# Flyback_schematic.net
KiCad netlist of a schematic drawn in Altium Designer
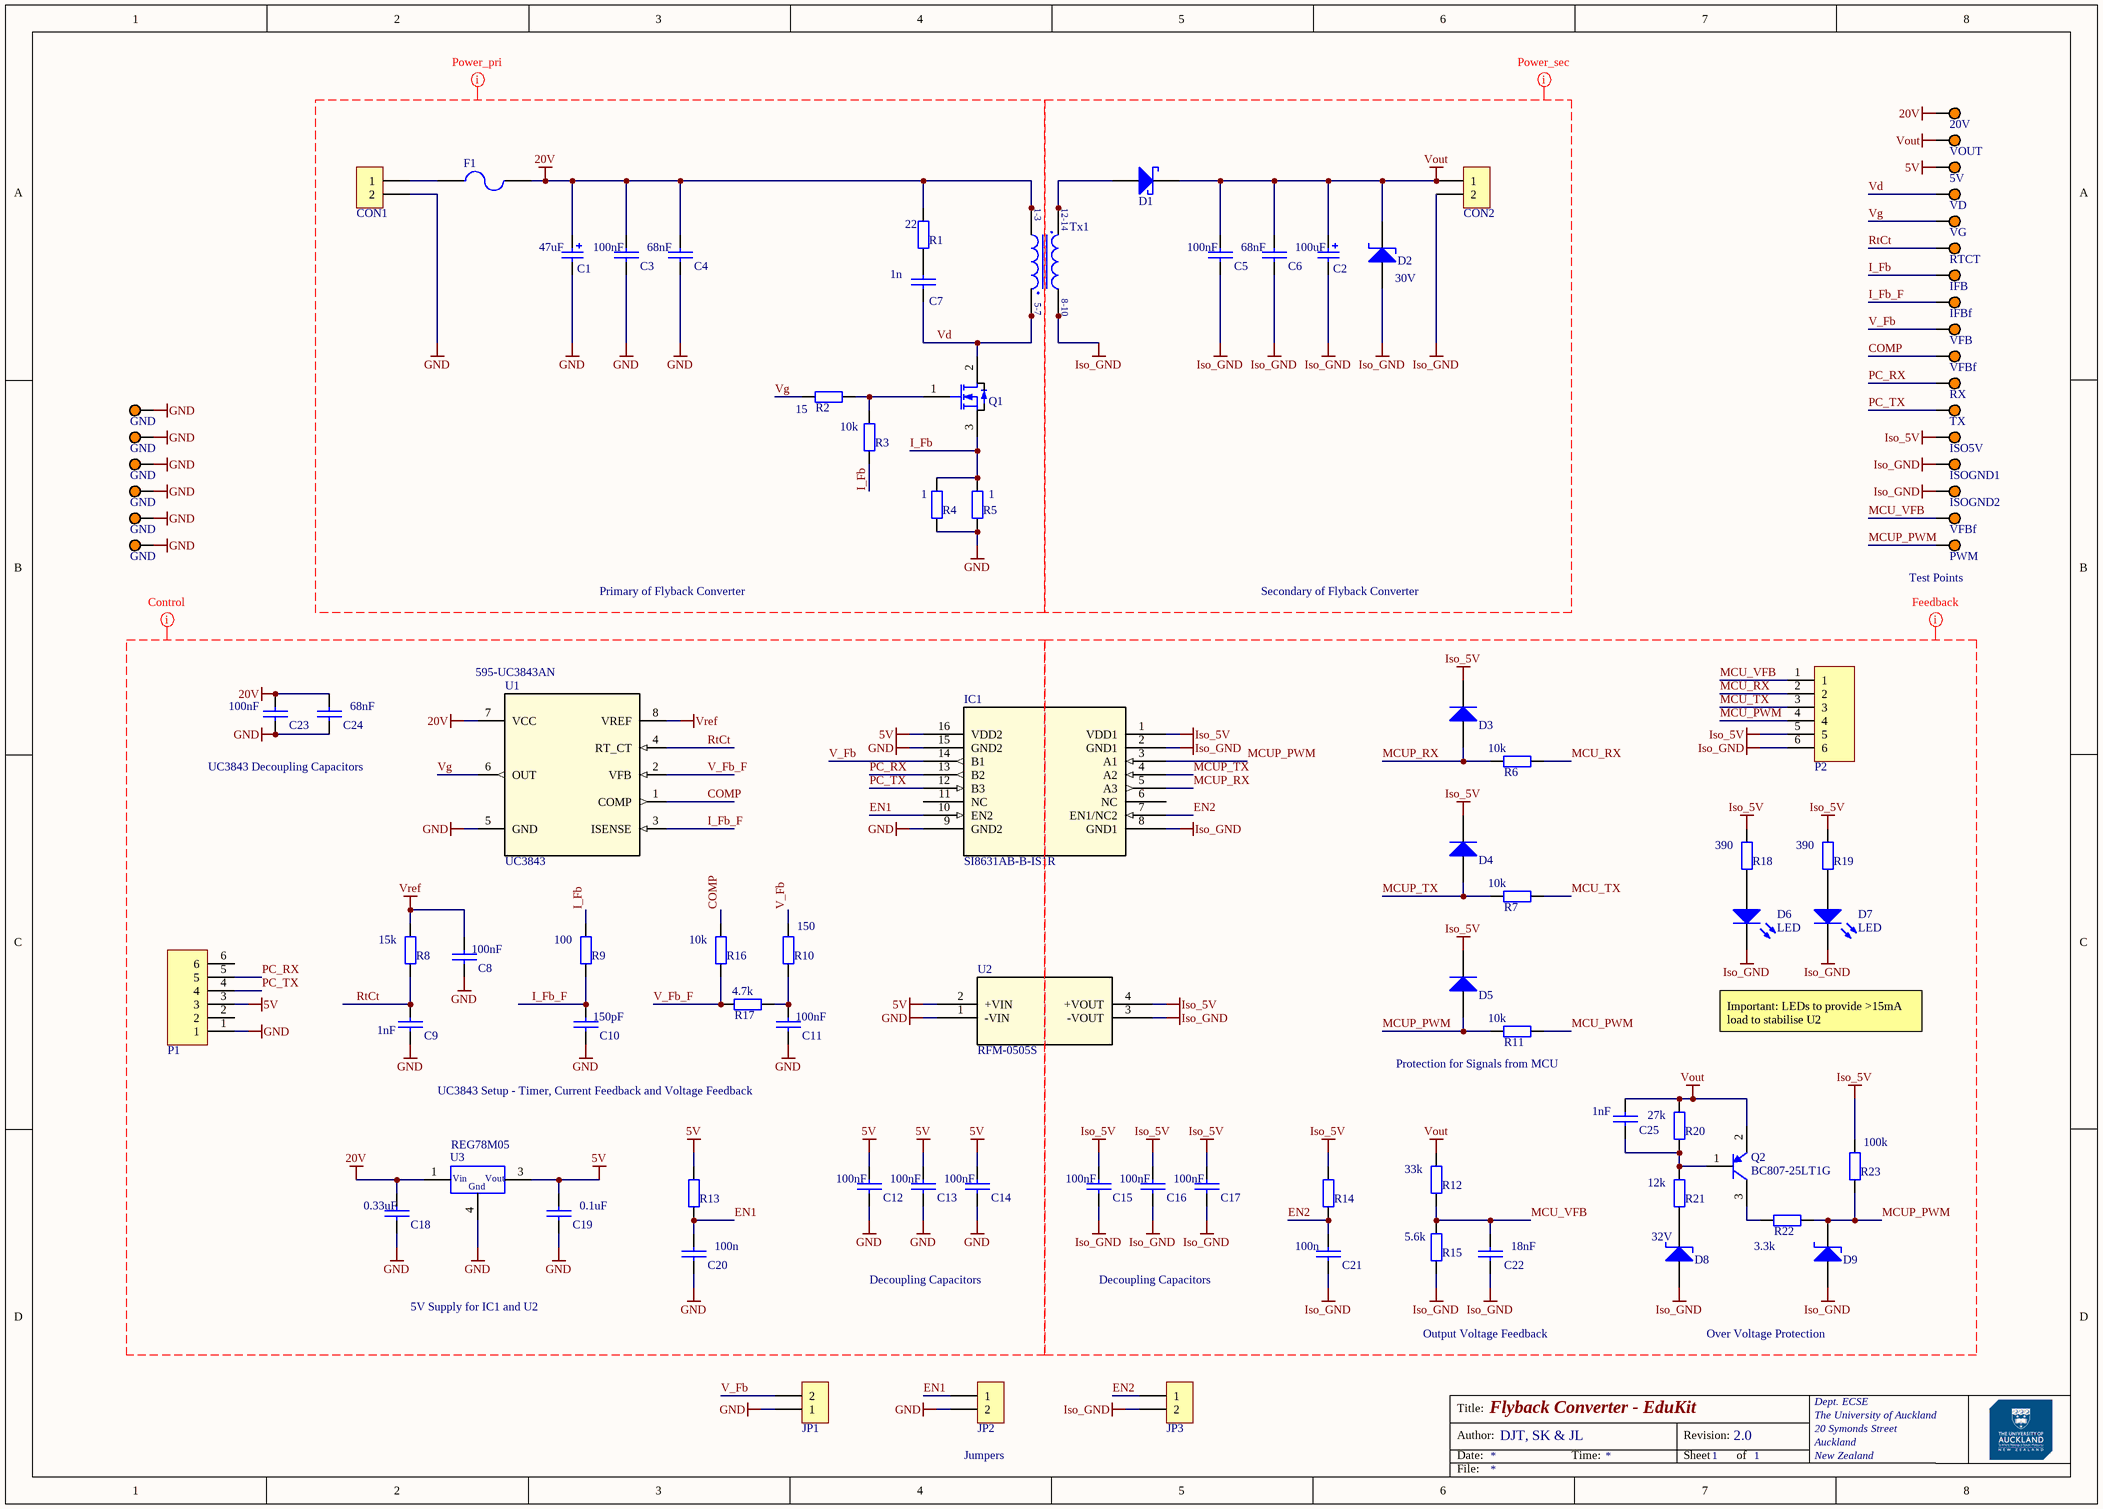
[diagram p0: Flyback_schematic.SchDoc]

(export (version "E")
  (design (tool "Eeschema 10.0.6"))
  (components
    (comp (ref "C1")
      (value "47uF")
      (footprint "CR05")
      (description "ECAP")
      (libsource (lib "EE311_library") (part "ECAP"))
    )
    (comp (ref "C2")
      (value "100uF")
      (footprint "CR05")
      (description "ECAP")
      (libsource (lib "EE311_library") (part "ECAP"))
    )
    (comp (ref "C3")
      (value "100nF")
      (footprint "C1210")
      (description "CCAP1210")
      (libsource (lib "EE311_library") (part "CCAP1210"))
    )
    (comp (ref "C4")
      (value "68nF")
      (footprint "C1210")
      (description "CCAP1210")
      (libsource (lib "EE311_library") (part "CCAP1210"))
    )
    (comp (ref "C5")
      (value "100nF")
      (footprint "C1210")
      (description "CCAP1210")
      (libsource (lib "EE311_library") (part "CCAP1210"))
    )
    (comp (ref "C6")
      (value "68nF")
      (footprint "C1210")
      (description "CCAP1210")
      (libsource (lib "EE311_library") (part "CCAP1210"))
    )
    (comp (ref "C7")
      (value "1n")
      (footprint "C1210")
      (description "CCAP1210")
      (libsource (lib "EE311_library") (part "CCAP1210"))
    )
    (comp (ref "C8")
      (value "100nF")
      (footprint "C0805")
      (description "CCAP0805")
      (libsource (lib "EE311_library") (part "CCAP0805"))
    )
    (comp (ref "C9")
      (value "1nF")
      (footprint "C0805")
      (description "CCAP0805")
      (libsource (lib "EE311_library") (part "CCAP0805"))
    )
    (comp (ref "C10")
      (value "150pF")
      (footprint "C0805")
      (description "CCAP0805")
      (libsource (lib "EE311_library") (part "CCAP0805"))
    )
    (comp (ref "C11")
      (value "100nF")
      (footprint "C0805")
      (description "CCAP0805")
      (libsource (lib "EE311_library") (part "CCAP0805"))
    )
    (comp (ref "C12")
      (value "100nF")
      (footprint "C0805")
      (description "CCAP0805")
      (libsource (lib "EE311_library") (part "CCAP0805"))
    )
    (comp (ref "C13")
      (value "100nF")
      (footprint "C0805")
      (description "CCAP0805")
      (libsource (lib "EE311_library") (part "CCAP0805"))
    )
    (comp (ref "C14")
      (value "100nF")
      (footprint "C0805")
      (description "CCAP0805")
      (libsource (lib "EE311_library") (part "CCAP0805"))
    )
    (comp (ref "C15")
      (value "100nF")
      (footprint "C0805")
      (description "CCAP0805")
      (libsource (lib "EE311_library") (part "CCAP0805"))
    )
    (comp (ref "C16")
      (value "100nF")
      (footprint "C0805")
      (description "CCAP0805")
      (libsource (lib "EE311_library") (part "CCAP0805"))
    )
    (comp (ref "C17")
      (value "100nF")
      (footprint "C0805")
      (description "CCAP0805")
      (libsource (lib "EE311_library") (part "CCAP0805"))
    )
    (comp (ref "C18")
      (value "0.33uF")
      (footprint "C0805")
      (description "CCAP0805")
      (libsource (lib "EE311_library") (part "CCAP0805"))
    )
    (comp (ref "C19")
      (value "0.1uF")
      (footprint "C0805")
      (description "CCAP0805")
      (libsource (lib "EE311_library") (part "CCAP0805"))
    )
    (comp (ref "C20")
      (value "100n")
      (footprint "C0805")
      (description "CCAP0805")
      (libsource (lib "EE311_library") (part "CCAP0805"))
    )
    (comp (ref "C21")
      (value "100n")
      (footprint "C0805")
      (description "CCAP0805")
      (libsource (lib "EE311_library") (part "CCAP0805"))
    )
    (comp (ref "C22")
      (value "18nF")
      (footprint "C0805")
      (description "CCAP0805")
      (libsource (lib "EE311_library") (part "CCAP0805"))
    )
    (comp (ref "C23")
      (value "100nF")
      (footprint "C0805")
      (description "CCAP0805")
      (libsource (lib "EE311_library") (part "CCAP0805"))
    )
    (comp (ref "C24")
      (value "68nF")
      (footprint "C0805")
      (description "CCAP0805")
      (libsource (lib "EE311_library") (part "CCAP0805"))
    )
    (comp (ref "C25")
      (value "1nF")
      (footprint "C0805")
      (description "CCAP0805")
      (libsource (lib "EE311_library") (part "CCAP0805"))
    )
    (comp (ref "CON1") (value "Header 2X1") (footprint "HDR2X1_5") (libsource (lib "") (part "HDR2X1_2")))
    (comp (ref "CON2") (value "Header 2X1") (footprint "HDR2X1_5") (libsource (lib "") (part "HDR2X1_1")))
    (comp (ref "D1")
      (value "SDT5H100P5")
      (footprint "PowerDI5")
      (description "Schottky Diode")
      (libsource (lib "EE311_library") (part "SDT5H100P5"))
    )
    (comp (ref "D2")
      (value "30V")
      (footprint "SOD123")
      (description "Zener Diode")
      (libsource (lib "EE311_library") (part "Zener"))
    )
    (comp (ref "D3")
      (value "1N4148")
      (footprint "SOD123")
      (description "Signal Diode - 1N4148")
      (libsource (lib "EE311_library") (part "1N4148"))
    )
    (comp (ref "D4")
      (value "1N4148")
      (footprint "SOD123")
      (description "Signal Diode - 1N4148")
      (libsource (lib "EE311_library") (part "1N4148"))
    )
    (comp (ref "D5")
      (value "1N4148")
      (footprint "SOD123")
      (description "Signal Diode - 1N4148")
      (libsource (lib "EE311_library") (part "1N4148"))
    )
    (comp (ref "D6") (value "LED") (footprint "LED0805") (libsource (lib "EE311_library") (part "LED")))
    (comp (ref "D7") (value "LED") (footprint "LED0805") (libsource (lib "EE311_library") (part "LED")))
    (comp (ref "D8")
      (value "32V")
      (footprint "SOD123")
      (description "Zener Diode")
      (libsource (lib "EE311_library") (part "Zener"))
    )
    (comp (ref "D9")
      (value "Zener")
      (footprint "SOD123")
      (description "Zener Diode")
      (libsource (lib "EE311_library") (part "Zener"))
    )
    (comp (ref "F1")
      (value "Fuse Resettable")
      (footprint "0ZCF Series")
      (description "PTC RESET FUSE 60V 1A 2920")
      (fields (field (name "MPN") "0ZCF0100AF2A") (field (name "MANUFACTURER") "Bel Fuse Inc."))
      (libsource (lib "EE311_library") (part "FuseResettable 0ZCF0100AF2A"))
    )
    (comp (ref "GND1")
      (value "GND")
      (footprint "Testpoint - 1mm")
      (description "Testpoint")
      (libsource (lib "EE311_symbols") (part "TP"))
    )
    (comp (ref "GND2")
      (value "GND")
      (footprint "Testpoint - 1mm")
      (description "Testpoint")
      (libsource (lib "EE311_symbols") (part "TP"))
    )
    (comp (ref "GND3")
      (value "GND")
      (footprint "Testpoint - 1mm")
      (description "Testpoint")
      (libsource (lib "EE311_symbols") (part "TP"))
    )
    (comp (ref "GND4")
      (value "GND")
      (footprint "Testpoint - 1mm")
      (description "Testpoint")
      (libsource (lib "EE311_symbols") (part "TP"))
    )
    (comp (ref "GND5")
      (value "GND")
      (footprint "Testpoint - 1mm")
      (description "Testpoint")
      (libsource (lib "EE311_symbols") (part "TP"))
    )
    (comp (ref "GND6")
      (value "GND")
      (footprint "Testpoint - 1mm")
      (description "Testpoint")
      (libsource (lib "EE311_symbols") (part "TP"))
    )
    (comp (ref "IC1")
      (value "SI8631AB-B-IS1R")
      (footprint "EE311_footprints:SOIC16")
      (description "No Description Available")
      (fields (field (name "COPYRIGHT") "Copyright (C) 2018 Accelerated Designs. All rights reserved"))
      (libsource (lib "EE311_symbols") (part "SI8631AB-B-IS1R"))
    )
    (comp (ref "JP1")
      (value "Header 2X1")
      (footprint "HDR2X1_2P54")
      (libsource (lib "EE311_library") (part "HDR2X1"))
    )
    (comp (ref "JP2") (value "Header 2X1") (footprint "HDR2X1_2P54") (libsource (lib "") (part "HDR2X1_1")))
    (comp (ref "JP3") (value "Header 2X1") (footprint "HDR2X1_2P54") (libsource (lib "") (part "HDR2X1_1")))
    (comp (ref "P1")
      (value "Header 6X1")
      (footprint "HDR6X1_2P54")
      (description "Header, 6-Pin")
      (fields (field (name "PUBLISHER") "Altium Limited"))
      (libsource (lib "") (part "HDR6X1_1"))
    )
    (comp (ref "P2")
      (value "Header 6X1")
      (footprint "HDR6X1_2P54")
      (description "Header, 6-Pin")
      (fields (field (name "PUBLISHER") "Altium Limited"))
      (libsource (lib "EE311_library") (part "HDR6X1"))
    )
    (comp (ref "Q1")
      (value "MOSFET")
      (footprint "TO220")
      (description "NFET TO220")
      (libsource (lib "EE311_symbols") (part "NFET1"))
    )
    (comp (ref "Q2")
      (value "BC807-25LT1G")
      (footprint "SOT23SM")
      (description "General Purpose Transistor, PNP Silicon, 3-Pin SOT-23, Pb-Free, Tape and Reel")
      (fields (field (name "MANUFACTURER") "On Semiconductor"))
      (libsource (lib "EE311_library") (part "BC807"))
    )
    (comp (ref "R1")
      (value "22")
      (footprint "R1206")
      (description "RES1206")
      (libsource (lib "EE311_library") (part "RES1206"))
    )
    (comp (ref "R2")
      (value "15")
      (footprint "R0805")
      (description "RES0805")
      (libsource (lib "") (part "RES0805_3"))
    )
    (comp (ref "R3")
      (value "10k")
      (footprint "R0805")
      (description "RES0805")
      (libsource (lib "EE311_library") (part "RES0805"))
    )
    (comp (ref "R4")
      (value "1")
      (footprint "R1206")
      (description "RES1206")
      (libsource (lib "EE311_library") (part "RES1206"))
    )
    (comp (ref "R5")
      (value "1")
      (footprint "R1206")
      (description "RES1206")
      (libsource (lib "EE311_library") (part "RES1206"))
    )
    (comp (ref "R6")
      (value "10k")
      (footprint "R0805")
      (description "RES0805")
      (libsource (lib "") (part "RES0805_1"))
    )
    (comp (ref "R7")
      (value "10k")
      (footprint "R0805")
      (description "RES0805")
      (libsource (lib "") (part "RES0805_1"))
    )
    (comp (ref "R8")
      (value "15k")
      (footprint "R0805")
      (description "RES0805")
      (libsource (lib "") (part "RES0805_2"))
    )
    (comp (ref "R9")
      (value "100")
      (footprint "R0805")
      (description "RES0805")
      (libsource (lib "EE311_library") (part "RES0805"))
    )
    (comp (ref "R10")
      (value "150")
      (footprint "R0805")
      (description "RES0805")
      (libsource (lib "EE311_library") (part "RES0805"))
    )
    (comp (ref "R11")
      (value "10k")
      (footprint "R0805")
      (description "RES0805")
      (libsource (lib "") (part "RES0805_1"))
    )
    (comp (ref "R12")
      (value "33k")
      (footprint "R0805")
      (description "RES0805")
      (libsource (lib "EE311_library") (part "RES0805"))
    )
    (comp (ref "R13")
      (value "Resistor 0805")
      (footprint "R0805")
      (description "RES0805")
      (libsource (lib "EE311_library") (part "RES0805"))
    )
    (comp (ref "R14")
      (value "Resistor 0805")
      (footprint "R0805")
      (description "RES0805")
      (libsource (lib "EE311_library") (part "RES0805"))
    )
    (comp (ref "R15")
      (value "5.6k")
      (footprint "R0805")
      (description "RES0805")
      (libsource (lib "EE311_library") (part "RES0805"))
    )
    (comp (ref "R16")
      (value "10k")
      (footprint "R0805")
      (description "RES0805")
      (libsource (lib "EE311_library") (part "RES0805"))
    )
    (comp (ref "R17")
      (value "4.7k")
      (footprint "R0805")
      (description "RES0805")
      (libsource (lib "") (part "RES0805_1"))
    )
    (comp (ref "R18")
      (value "390")
      (footprint "R0805")
      (description "RES0805")
      (libsource (lib "EE311_library") (part "RES0805"))
    )
    (comp (ref "R19")
      (value "390")
      (footprint "R0805")
      (description "RES0805")
      (libsource (lib "EE311_library") (part "RES0805"))
    )
    (comp (ref "R20")
      (value "27k")
      (footprint "R0805")
      (description "RES0805")
      (libsource (lib "EE311_library") (part "RES0805"))
    )
    (comp (ref "R21")
      (value "12k")
      (footprint "R0805")
      (description "RES0805")
      (libsource (lib "EE311_library") (part "RES0805"))
    )
    (comp (ref "R22")
      (value "3.3k")
      (footprint "R0805")
      (description "RES0805")
      (libsource (lib "") (part "RES0805_3"))
    )
    (comp (ref "R23")
      (value "100k")
      (footprint "R0805")
      (description "RES0805")
      (libsource (lib "EE311_library") (part "RES0805"))
    )
    (comp (ref "TP1")
      (value "20V")
      (footprint "Testpoint - 1mm")
      (description "Testpoint")
      (libsource (lib "EE311_symbols") (part "TP"))
    )
    (comp (ref "TP2")
      (value "VOUT")
      (footprint "Testpoint - 1mm")
      (description "Testpoint")
      (libsource (lib "EE311_symbols") (part "TP"))
    )
    (comp (ref "TP3")
      (value "VG")
      (footprint "Testpoint - 1mm")
      (description "Testpoint")
      (libsource (lib "EE311_symbols") (part "TP"))
    )
    (comp (ref "TP4")
      (value "PWM")
      (footprint "Testpoint - 1mm")
      (description "Testpoint")
      (libsource (lib "EE311_symbols") (part "TP"))
    )
    (comp (ref "TP6")
      (value "IFB")
      (footprint "Testpoint - 1mm")
      (description "Testpoint")
      (libsource (lib "EE311_symbols") (part "TP"))
    )
    (comp (ref "TP7")
      (value "VFB")
      (footprint "Testpoint - 1mm")
      (description "Testpoint")
      (libsource (lib "EE311_symbols") (part "TP"))
    )
    (comp (ref "TP8")
      (value "RX")
      (footprint "Testpoint - 1mm")
      (description "Testpoint")
      (libsource (lib "EE311_symbols") (part "TP"))
    )
    (comp (ref "TP9")
      (value "5V")
      (footprint "Testpoint - 1mm")
      (description "Testpoint")
      (libsource (lib "EE311_symbols") (part "TP"))
    )
    (comp (ref "TP10")
      (value "ISO5V")
      (footprint "Testpoint - 1mm")
      (description "Testpoint")
      (libsource (lib "EE311_symbols") (part "TP"))
    )
    (comp (ref "TP11")
      (value "ISOGND1")
      (footprint "Testpoint - 1mm")
      (description "Testpoint")
      (libsource (lib "EE311_symbols") (part "TP"))
    )
    (comp (ref "TP12")
      (value "TX")
      (footprint "Testpoint - 1mm")
      (description "Testpoint")
      (libsource (lib "EE311_symbols") (part "TP"))
    )
    (comp (ref "TP13")
      (value "ISOGND2")
      (footprint "Testpoint - 1mm")
      (description "Testpoint")
      (libsource (lib "EE311_symbols") (part "TP"))
    )
    (comp (ref "TP14")
      (value "RTCT")
      (footprint "Testpoint - 1mm")
      (description "Testpoint")
      (libsource (lib "EE311_symbols") (part "TP"))
    )
    (comp (ref "TP15")
      (value "IFBf")
      (footprint "Testpoint - 1mm")
      (description "Testpoint")
      (libsource (lib "EE311_symbols") (part "TP"))
    )
    (comp (ref "TP16")
      (value "VFBf")
      (footprint "Testpoint - 1mm")
      (description "Testpoint")
      (libsource (lib "EE311_symbols") (part "TP"))
    )
    (comp (ref "TP17")
      (value "VFBf")
      (footprint "Testpoint - 1mm")
      (description "Testpoint")
      (libsource (lib "EE311_symbols") (part "TP"))
    )
    (comp (ref "Tx1")
      (value "Inductor")
      (footprint "ETD34")
      (description "Inductor with core")
      (libsource (lib "EE311_library") (part "Transformer EFD34"))
    )
    (comp (ref "U1")
      (value "UC3843")
      (footprint "DIP-8")
      (description "No Description Available")
      (fields
        (field (name "PARTNUMBER") "UC3843N")
        (field (name "MANUFACTURER") "Texas Instruments")
        (field (name "SUPPLIER PART NUMBER 1") "595-UC3843AN")
        (field (name "COPYRIGHT") "Copyright (C) 2018 Accelerated Designs. All rights reserved")
      )
      (libsource (lib "EE311_library") (part "UC3843"))
    )
    (comp (ref "U2")
      (value "RFM-0505S")
      (footprint "RFM-0505S_RCP")
      (description "No Description Available")
      (fields (field (name "COPYRIGHT") "Copyright (C) 2018 Accelerated Designs. All rights reserved"))
      (libsource (lib "EE311_library") (part "RFM-0505S"))
    )
    (comp (ref "U3")
      (value "REG78M05")
      (footprint "TO252")
      (description "78M Series Linear Regulators")
      (libsource (lib "EE311_library") (part "REG78MXX"))
    )
    (comp (ref "VD")
      (value "VD")
      (footprint "Testpoint - 1mm")
      (description "Testpoint")
      (libsource (lib "EE311_symbols") (part "TP"))
    )
  )
  (nets
    (net (code "1") (name "/COMP") (class "Default")
      (node (ref "R16") (pin "2") (pinfunction "2_2") (pintype "passive"))
      (node (ref "TP16") (pin "1") (pinfunction "1_1") (pintype "passive"))
      (node (ref "U1") (pin "1") (pinfunction "COMP_1") (pintype "output"))
    )
    (net (code "2") (name "/EN1") (class "Default")
      (node (ref "C20") (pin "2") (pinfunction "2_2") (pintype "passive"))
      (node (ref "IC1") (pin "10") (pinfunction "EN2_10") (pintype "input"))
      (node (ref "JP2") (pin "1") (pinfunction "1_1") (pintype "passive"))
      (node (ref "R13") (pin "1") (pinfunction "1_1") (pintype "passive"))
    )
    (net (code "3") (name "/EN2") (class "Default")
      (node (ref "C21") (pin "2") (pinfunction "2_2") (pintype "passive"))
      (node (ref "IC1") (pin "7") (pinfunction "EN1/NC2_7") (pintype "input"))
      (node (ref "JP3") (pin "1") (pinfunction "1_1") (pintype "passive"))
      (node (ref "R14") (pin "1") (pinfunction "1_1") (pintype "passive"))
    )
    (net (code "4") (name "/I_Fb") (class "Default")
      (node (ref "Q1") (pin "3") (pinfunction "S_3") (pintype "passive"))
      (node (ref "R3") (pin "1") (pinfunction "1_1") (pintype "passive"))
      (node (ref "R4") (pin "2") (pinfunction "2_2") (pintype "passive"))
      (node (ref "R5") (pin "2") (pinfunction "2_2") (pintype "passive"))
      (node (ref "R9") (pin "2") (pinfunction "2_2") (pintype "passive"))
      (node (ref "TP6") (pin "1") (pinfunction "1_1") (pintype "passive"))
    )
    (net (code "5") (name "/I_Fb_F") (class "Default")
      (node (ref "C10") (pin "2") (pinfunction "2_2") (pintype "passive"))
      (node (ref "R9") (pin "1") (pinfunction "1_1") (pintype "passive"))
      (node (ref "TP15") (pin "1") (pinfunction "1_1") (pintype "passive"))
      (node (ref "U1") (pin "3") (pinfunction "ISENSE_3") (pintype "input"))
    )
    (net (code "6") (name "/MCUP_PWM") (class "Default")
      (node (ref "D5") (pin "1") (pinfunction "1_1") (pintype "passive"))
      (node (ref "D9") (pin "2") (pinfunction "K_2") (pintype "passive"))
      (node (ref "IC1") (pin "3") (pinfunction "A1_3") (pintype "input"))
      (node (ref "R11") (pin "2") (pinfunction "2_2") (pintype "passive"))
      (node (ref "R22") (pin "2") (pinfunction "2_2") (pintype "passive"))
      (node (ref "R23") (pin "1") (pinfunction "1_1") (pintype "passive"))
      (node (ref "TP4") (pin "1") (pinfunction "1_1") (pintype "passive"))
    )
    (net (code "7") (name "/MCUP_RX") (class "Default")
      (node (ref "D3") (pin "1") (pinfunction "1_1") (pintype "passive"))
      (node (ref "IC1") (pin "5") (pinfunction "A3_5") (pintype "output"))
      (node (ref "R6") (pin "2") (pinfunction "2_2") (pintype "passive"))
    )
    (net (code "8") (name "/MCUP_TX") (class "Default")
      (node (ref "D4") (pin "1") (pinfunction "1_1") (pintype "passive"))
      (node (ref "IC1") (pin "4") (pinfunction "A2_4") (pintype "input"))
      (node (ref "R7") (pin "2") (pinfunction "2_2") (pintype "passive"))
    )
    (net (code "9") (name "/MCU_PWM") (class "Default")
      (node (ref "P2") (pin "4") (pinfunction "4_4") (pintype "passive"))
      (node (ref "R11") (pin "1") (pinfunction "1_1") (pintype "passive"))
    )
    (net (code "10") (name "/MCU_RX") (class "Default")
      (node (ref "P2") (pin "2") (pinfunction "2_2") (pintype "passive"))
      (node (ref "R6") (pin "1") (pinfunction "1_1") (pintype "passive"))
    )
    (net (code "11") (name "/MCU_TX") (class "Default")
      (node (ref "P2") (pin "3") (pinfunction "3_3") (pintype "passive"))
      (node (ref "R7") (pin "1") (pinfunction "1_1") (pintype "passive"))
    )
    (net (code "12") (name "/MCU_VFB") (class "Default")
      (node (ref "C22") (pin "2") (pinfunction "2_2") (pintype "passive"))
      (node (ref "P2") (pin "1") (pinfunction "1_1") (pintype "passive"))
      (node (ref "R12") (pin "1") (pinfunction "1_1") (pintype "passive"))
      (node (ref "R15") (pin "2") (pinfunction "2_2") (pintype "passive"))
      (node (ref "TP17") (pin "1") (pinfunction "1_1") (pintype "passive"))
    )
    (net (code "13") (name "/PC_RX") (class "Default")
      (node (ref "IC1") (pin "13") (pinfunction "B2_13") (pintype "output"))
      (node (ref "P1") (pin "5") (pinfunction "5_5") (pintype "passive"))
      (node (ref "TP8") (pin "1") (pinfunction "1_1") (pintype "passive"))
    )
    (net (code "14") (name "/PC_TX") (class "Default")
      (node (ref "IC1") (pin "12") (pinfunction "B3_12") (pintype "input"))
      (node (ref "P1") (pin "4") (pinfunction "4_4") (pintype "passive"))
      (node (ref "TP12") (pin "1") (pinfunction "1_1") (pintype "passive"))
    )
    (net (code "15") (name "/RtCt") (class "Default")
      (node (ref "C9") (pin "2") (pinfunction "2_2") (pintype "passive"))
      (node (ref "R8") (pin "2") (pinfunction "2_2") (pintype "passive"))
      (node (ref "TP14") (pin "1") (pinfunction "1_1") (pintype "passive"))
      (node (ref "U1") (pin "4") (pinfunction "RT_CT_4") (pintype "input"))
    )
    (net (code "16") (name "/V_Fb") (class "Default")
      (node (ref "IC1") (pin "14") (pinfunction "B1_14") (pintype "output"))
      (node (ref "JP1") (pin "2") (pinfunction "2_2") (pintype "passive"))
      (node (ref "R10") (pin "2") (pinfunction "2_2") (pintype "passive"))
      (node (ref "TP7") (pin "1") (pinfunction "1_1") (pintype "passive"))
    )
    (net (code "17") (name "/V_Fb_F") (class "Default")
      (node (ref "R16") (pin "1") (pinfunction "1_1") (pintype "passive"))
      (node (ref "R17") (pin "2") (pinfunction "2_2") (pintype "passive"))
      (node (ref "U1") (pin "2") (pinfunction "VFB_2") (pintype "input"))
    )
    (net (code "18") (name "/Vd") (class "Default")
      (node (ref "C7") (pin "1") (pinfunction "1_1") (pintype "passive"))
      (node (ref "Q1") (pin "2") (pinfunction "D_2") (pintype "passive"))
      (node (ref "Tx1") (pin "5") (pinfunction "5_5") (pintype "passive"))
      (node (ref "Tx1") (pin "6") (pinfunction "6_6") (pintype "passive"))
      (node (ref "Tx1") (pin "7") (pinfunction "7_7") (pintype "passive"))
      (node (ref "VD") (pin "1") (pinfunction "1_1") (pintype "passive"))
    )
    (net (code "19") (name "/Vg") (class "Default")
      (node (ref "R2") (pin "1") (pinfunction "1_1") (pintype "passive"))
      (node (ref "TP3") (pin "1") (pinfunction "1_1") (pintype "passive"))
      (node (ref "U1") (pin "6") (pinfunction "OUT_6") (pintype "output"))
    )
    (net (code "20") (name "5V") (class "Default")
      (node (ref "C12") (pin "2") (pinfunction "2_2") (pintype "passive"))
      (node (ref "C13") (pin "2") (pinfunction "2_2") (pintype "passive"))
      (node (ref "C14") (pin "2") (pinfunction "2_2") (pintype "passive"))
      (node (ref "C19") (pin "2") (pinfunction "2_2") (pintype "passive"))
      (node (ref "IC1") (pin "16") (pinfunction "VDD2_16") (pintype "power_in"))
      (node (ref "P1") (pin "3") (pinfunction "3_3") (pintype "passive"))
      (node (ref "R13") (pin "2") (pinfunction "2_2") (pintype "passive"))
      (node (ref "TP9") (pin "1") (pinfunction "1_1") (pintype "passive"))
      (node (ref "U2") (pin "2") (pinfunction "+VIN_2") (pintype "power_in"))
      (node (ref "U3") (pin "3") (pinfunction "Vout_3") (pintype "passive"))
    )
    (net (code "21") (name "20V") (class "Default")
      (node (ref "C1") (pin "1") (pinfunction "1_1") (pintype "passive"))
      (node (ref "C18") (pin "2") (pinfunction "2_2") (pintype "passive"))
      (node (ref "C23") (pin "2") (pinfunction "2_2") (pintype "passive"))
      (node (ref "C24") (pin "2") (pinfunction "2_2") (pintype "passive"))
      (node (ref "C3") (pin "2") (pinfunction "2_2") (pintype "passive"))
      (node (ref "C4") (pin "2") (pinfunction "2_2") (pintype "passive"))
      (node (ref "F1") (pin "2") (pinfunction "2_2") (pintype "passive"))
      (node (ref "R1") (pin "2") (pinfunction "2_2") (pintype "passive"))
      (node (ref "TP1") (pin "1") (pinfunction "1_1") (pintype "passive"))
      (node (ref "Tx1") (pin "1") (pinfunction "1_1") (pintype "passive"))
      (node (ref "Tx1") (pin "2") (pinfunction "2_2") (pintype "passive"))
      (node (ref "Tx1") (pin "3") (pinfunction "3_3") (pintype "passive"))
      (node (ref "U1") (pin "7") (pinfunction "VCC_7") (pintype "power_in"))
      (node (ref "U3") (pin "1") (pinfunction "Vin_1") (pintype "passive"))
    )
    (net (code "22") (name "GND") (class "Default")
      (node (ref "C1") (pin "2") (pinfunction "2_2") (pintype "passive"))
      (node (ref "C10") (pin "1") (pinfunction "1_1") (pintype "passive"))
      (node (ref "C11") (pin "1") (pinfunction "1_1") (pintype "passive"))
      (node (ref "C12") (pin "1") (pinfunction "1_1") (pintype "passive"))
      (node (ref "C13") (pin "1") (pinfunction "1_1") (pintype "passive"))
      (node (ref "C14") (pin "1") (pinfunction "1_1") (pintype "passive"))
      (node (ref "C18") (pin "1") (pinfunction "1_1") (pintype "passive"))
      (node (ref "C19") (pin "1") (pinfunction "1_1") (pintype "passive"))
      (node (ref "C20") (pin "1") (pinfunction "1_1") (pintype "passive"))
      (node (ref "C23") (pin "1") (pinfunction "1_1") (pintype "passive"))
      (node (ref "C24") (pin "1") (pinfunction "1_1") (pintype "passive"))
      (node (ref "C3") (pin "1") (pinfunction "1_1") (pintype "passive"))
      (node (ref "C4") (pin "1") (pinfunction "1_1") (pintype "passive"))
      (node (ref "C8") (pin "1") (pinfunction "1_1") (pintype "passive"))
      (node (ref "C9") (pin "1") (pinfunction "1_1") (pintype "passive"))
      (node (ref "CON1") (pin "2") (pinfunction "2_2") (pintype "passive"))
      (node (ref "GND1") (pin "1") (pinfunction "1_1") (pintype "passive"))
      (node (ref "GND2") (pin "1") (pinfunction "1_1") (pintype "passive"))
      (node (ref "GND3") (pin "1") (pinfunction "1_1") (pintype "passive"))
      (node (ref "GND4") (pin "1") (pinfunction "1_1") (pintype "passive"))
      (node (ref "GND5") (pin "1") (pinfunction "1_1") (pintype "passive"))
      (node (ref "GND6") (pin "1") (pinfunction "1_1") (pintype "passive"))
      (node (ref "IC1") (pin "15") (pinfunction "GND2_15") (pintype "passive"))
      (node (ref "IC1") (pin "9") (pinfunction "GND2_9") (pintype "passive"))
      (node (ref "JP1") (pin "1") (pinfunction "1_1") (pintype "passive"))
      (node (ref "JP2") (pin "2") (pinfunction "2_2") (pintype "passive"))
      (node (ref "P1") (pin "1") (pinfunction "1_1") (pintype "passive"))
      (node (ref "R4") (pin "1") (pinfunction "1_1") (pintype "passive"))
      (node (ref "R5") (pin "1") (pinfunction "1_1") (pintype "passive"))
      (node (ref "U1") (pin "5") (pinfunction "GND_5") (pintype "power_in"))
      (node (ref "U2") (pin "1") (pinfunction "-VIN_1") (pintype "passive"))
      (node (ref "U3") (pin "4") (pinfunction "Gnd_4") (pintype "passive"))
    )
    (net (code "23") (name "Iso_5V") (class "Default")
      (node (ref "C15") (pin "2") (pinfunction "2_2") (pintype "passive"))
      (node (ref "C16") (pin "2") (pinfunction "2_2") (pintype "passive"))
      (node (ref "C17") (pin "2") (pinfunction "2_2") (pintype "passive"))
      (node (ref "D3") (pin "2") (pinfunction "2_2") (pintype "passive"))
      (node (ref "D4") (pin "2") (pinfunction "2_2") (pintype "passive"))
      (node (ref "D5") (pin "2") (pinfunction "2_2") (pintype "passive"))
      (node (ref "IC1") (pin "1") (pinfunction "VDD1_1") (pintype "power_in"))
      (node (ref "P2") (pin "5") (pinfunction "5_5") (pintype "passive"))
      (node (ref "R14") (pin "2") (pinfunction "2_2") (pintype "passive"))
      (node (ref "R18") (pin "2") (pinfunction "2_2") (pintype "passive"))
      (node (ref "R19") (pin "2") (pinfunction "2_2") (pintype "passive"))
      (node (ref "R23") (pin "2") (pinfunction "2_2") (pintype "passive"))
      (node (ref "TP10") (pin "1") (pinfunction "1_1") (pintype "passive"))
      (node (ref "U2") (pin "4") (pinfunction "+VOUT_4") (pintype "power_in"))
    )
    (net (code "24") (name "Iso_GND") (class "Default")
      (node (ref "C15") (pin "1") (pinfunction "1_1") (pintype "passive"))
      (node (ref "C16") (pin "1") (pinfunction "1_1") (pintype "passive"))
      (node (ref "C17") (pin "1") (pinfunction "1_1") (pintype "passive"))
      (node (ref "C2") (pin "2") (pinfunction "2_2") (pintype "passive"))
      (node (ref "C21") (pin "1") (pinfunction "1_1") (pintype "passive"))
      (node (ref "C22") (pin "1") (pinfunction "1_1") (pintype "passive"))
      (node (ref "C5") (pin "1") (pinfunction "1_1") (pintype "passive"))
      (node (ref "C6") (pin "1") (pinfunction "1_1") (pintype "passive"))
      (node (ref "CON2") (pin "2") (pinfunction "2_2") (pintype "passive"))
      (node (ref "D2") (pin "1") (pinfunction "A_1") (pintype "passive"))
      (node (ref "D6") (pin "2") (pinfunction "K_2") (pintype "passive"))
      (node (ref "D7") (pin "2") (pinfunction "K_2") (pintype "passive"))
      (node (ref "D8") (pin "1") (pinfunction "A_1") (pintype "passive"))
      (node (ref "D9") (pin "1") (pinfunction "A_1") (pintype "passive"))
      (node (ref "IC1") (pin "2") (pinfunction "GND1_2") (pintype "passive"))
      (node (ref "IC1") (pin "8") (pinfunction "GND1_8") (pintype "passive"))
      (node (ref "JP3") (pin "2") (pinfunction "2_2") (pintype "passive"))
      (node (ref "P2") (pin "6") (pinfunction "6_6") (pintype "passive"))
      (node (ref "R15") (pin "1") (pinfunction "1_1") (pintype "passive"))
      (node (ref "TP11") (pin "1") (pinfunction "1_1") (pintype "passive"))
      (node (ref "TP13") (pin "1") (pinfunction "1_1") (pintype "passive"))
      (node (ref "Tx1") (pin "10") (pinfunction "10_10") (pintype "passive"))
      (node (ref "Tx1") (pin "8") (pinfunction "8_8") (pintype "passive"))
      (node (ref "Tx1") (pin "9") (pinfunction "9_9") (pintype "passive"))
      (node (ref "U2") (pin "3") (pinfunction "-VOUT_3") (pintype "passive"))
    )
    (net (code "25") (name "Net-(C7-Pad2)") (class "Default")
      (node (ref "C7") (pin "2") (pinfunction "2_2") (pintype "passive"))
      (node (ref "R1") (pin "1") (pinfunction "1_1") (pintype "passive"))
    )
    (net (code "26") (name "Net-(C11-Pad2)") (class "Default")
      (node (ref "C11") (pin "2") (pinfunction "2_2") (pintype "passive"))
      (node (ref "R10") (pin "1") (pinfunction "1_1") (pintype "passive"))
      (node (ref "R17") (pin "1") (pinfunction "1_1") (pintype "passive"))
    )
    (net (code "27") (name "Net-(CON1-Pad1)") (class "Default")
      (node (ref "CON1") (pin "1") (pinfunction "1_1") (pintype "passive"))
      (node (ref "F1") (pin "1") (pinfunction "1_1") (pintype "passive"))
    )
    (net (code "28") (name "Net-(D1-A)") (class "Default")
      (node (ref "D1") (pin "1") (pinfunction "A_1") (pintype "passive"))
      (node (ref "Tx1") (pin "12") (pinfunction "12_12") (pintype "passive"))
      (node (ref "Tx1") (pin "13") (pinfunction "13_13") (pintype "passive"))
      (node (ref "Tx1") (pin "14") (pinfunction "14_14") (pintype "passive"))
    )
    (net (code "29") (name "Net-(D6-A)") (class "Default")
      (node (ref "D6") (pin "1") (pinfunction "A_1") (pintype "passive"))
      (node (ref "R18") (pin "1") (pinfunction "1_1") (pintype "passive"))
    )
    (net (code "30") (name "Net-(D7-A)") (class "Default")
      (node (ref "D7") (pin "1") (pinfunction "A_1") (pintype "passive"))
      (node (ref "R19") (pin "1") (pinfunction "1_1") (pintype "passive"))
    )
    (net (code "31") (name "Net-(D8-K)") (class "Default")
      (node (ref "D8") (pin "2") (pinfunction "K_2") (pintype "passive"))
      (node (ref "R21") (pin "1") (pinfunction "1_1") (pintype "passive"))
    )
    (net (code "32") (name "Net-(Q1-G)") (class "Default")
      (node (ref "Q1") (pin "1") (pinfunction "G_1") (pintype "passive"))
      (node (ref "R2") (pin "2") (pinfunction "2_2") (pintype "passive"))
      (node (ref "R3") (pin "2") (pinfunction "2_2") (pintype "passive"))
    )
    (net (code "33") (name "Net-(Q2-B)") (class "Default")
      (node (ref "C25") (pin "1") (pinfunction "1_1") (pintype "passive"))
      (node (ref "Q2") (pin "1") (pinfunction "B_1") (pintype "passive"))
      (node (ref "R20") (pin "1") (pinfunction "1_1") (pintype "passive"))
      (node (ref "R21") (pin "2") (pinfunction "2_2") (pintype "passive"))
    )
    (net (code "34") (name "Net-(Q2-C)") (class "Default")
      (node (ref "Q2") (pin "3") (pinfunction "C_3") (pintype "passive"))
      (node (ref "R22") (pin "1") (pinfunction "1_1") (pintype "passive"))
    )
    (net (code "35") (name "Vout") (class "Default")
      (node (ref "C2") (pin "1") (pinfunction "1_1") (pintype "passive"))
      (node (ref "C25") (pin "2") (pinfunction "2_2") (pintype "passive"))
      (node (ref "C5") (pin "2") (pinfunction "2_2") (pintype "passive"))
      (node (ref "C6") (pin "2") (pinfunction "2_2") (pintype "passive"))
      (node (ref "CON2") (pin "1") (pinfunction "1_1") (pintype "passive"))
      (node (ref "D1") (pin "3") (pinfunction "K_3") (pintype "passive"))
      (node (ref "D2") (pin "2") (pinfunction "K_2") (pintype "passive"))
      (node (ref "Q2") (pin "2") (pinfunction "E_2") (pintype "passive"))
      (node (ref "R12") (pin "2") (pinfunction "2_2") (pintype "passive"))
      (node (ref "R20") (pin "2") (pinfunction "2_2") (pintype "passive"))
      (node (ref "TP2") (pin "1") (pinfunction "1_1") (pintype "passive"))
    )
    (net (code "36") (name "Vref") (class "Default")
      (node (ref "C8") (pin "2") (pinfunction "2_2") (pintype "passive"))
      (node (ref "R8") (pin "1") (pinfunction "1_1") (pintype "passive"))
      (node (ref "U1") (pin "8") (pinfunction "VREF_8") (pintype "power_in"))
    )
    (net (code "37") (name "unconnected-(IC1-NC-Pad6)") (class "Default")
      (node (ref "IC1") (pin "6") (pinfunction "NC_6") (pintype "passive"))
    )
    (net (code "38") (name "unconnected-(IC1-NC-Pad11)") (class "Default")
      (node (ref "IC1") (pin "11") (pinfunction "NC_11") (pintype "passive"))
    )
    (net (code "39") (name "unconnected-(P1-Pad2)") (class "Default")
      (node (ref "P1") (pin "2") (pinfunction "2_2") (pintype "passive"))
    )
    (net (code "40") (name "unconnected-(P1-Pad6)") (class "Default")
      (node (ref "P1") (pin "6") (pinfunction "6_6") (pintype "passive"))
    )
  )
)
